# APM-PX-Adapter.net
KiCad netlist of a schematic drawn in EAGLE
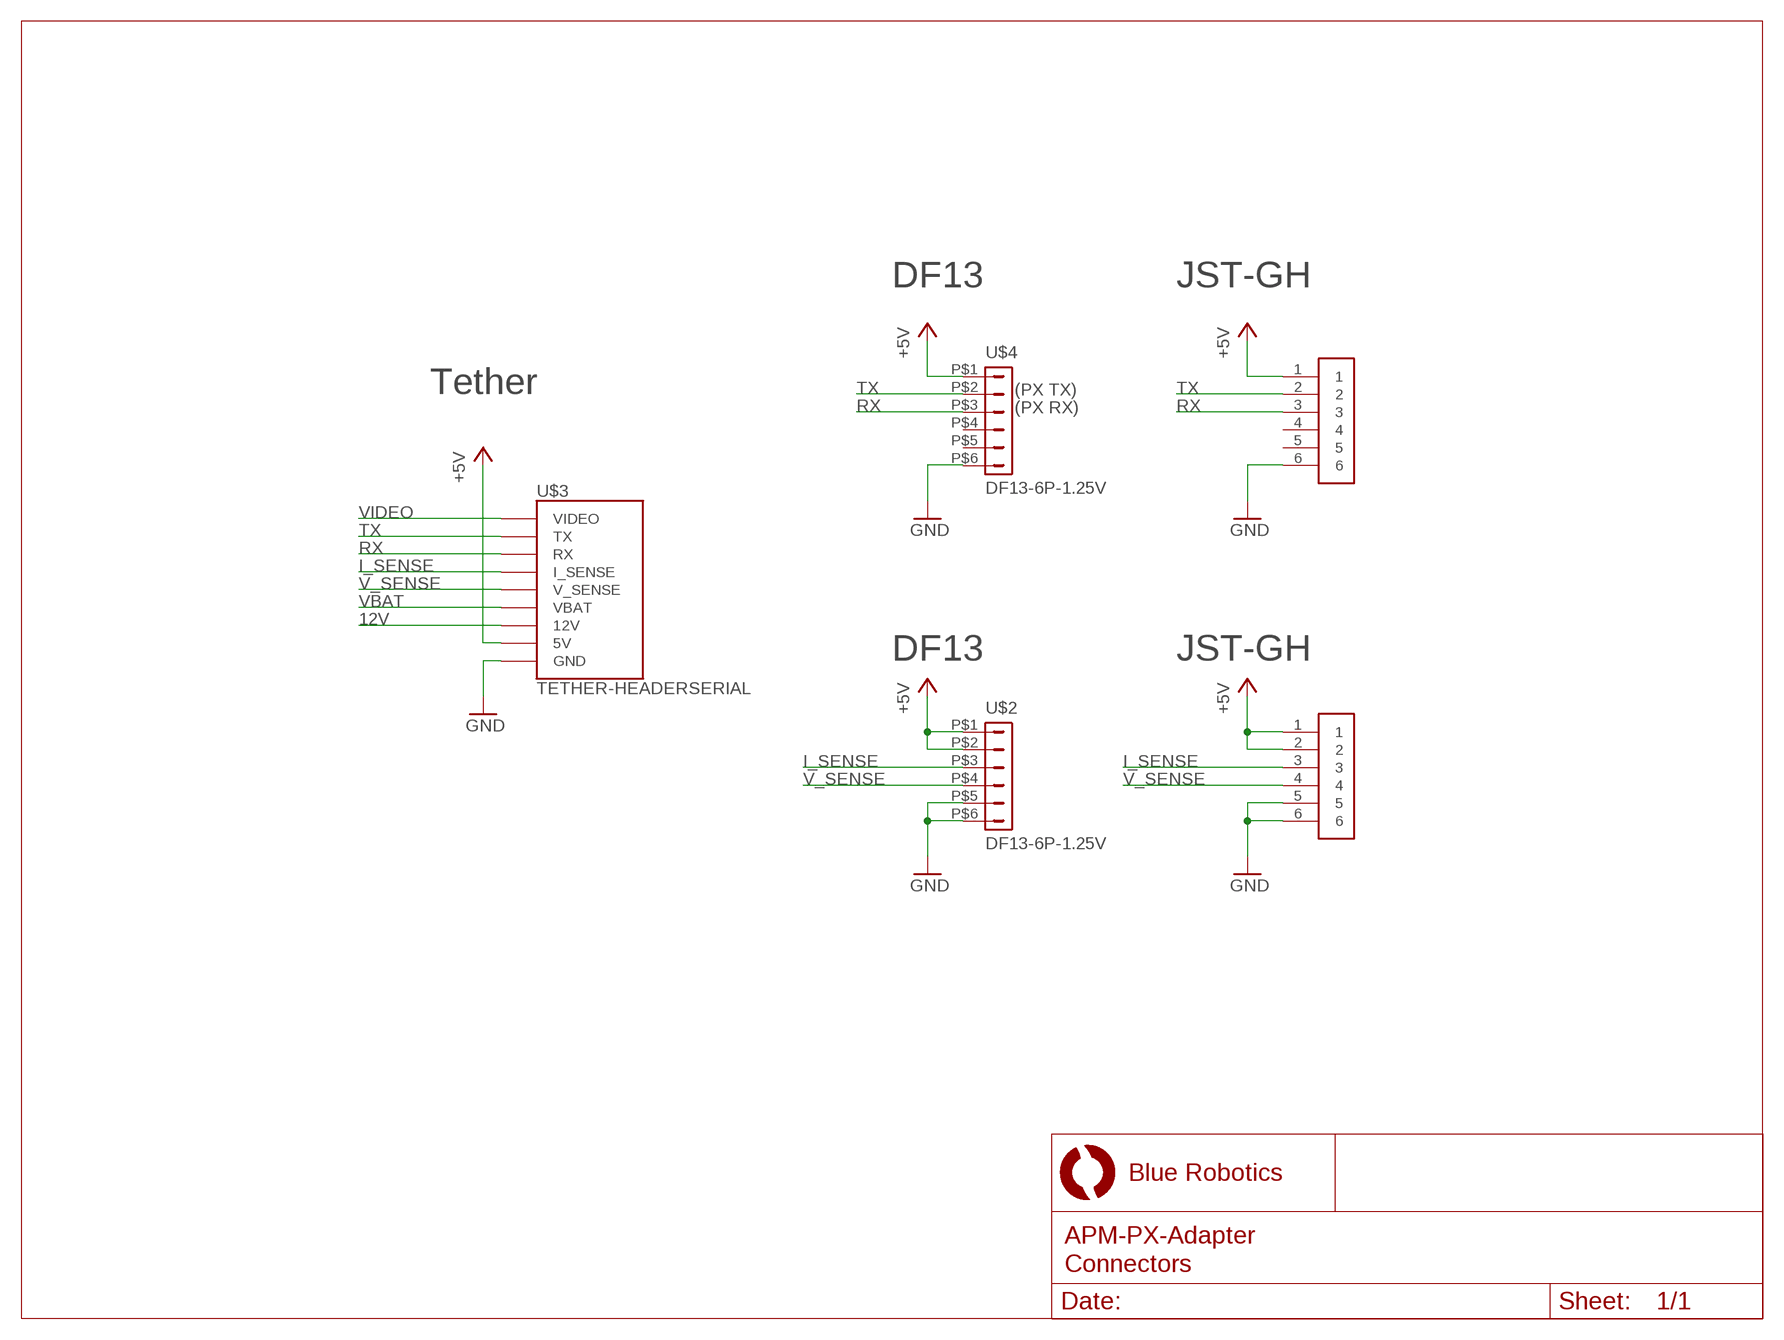
[diagram p0: schematic, sheet 1]

(export (version "E")
  (design (tool "Eeschema 10.0.6"))
  (components
    (comp (ref "U$1")
      (value "JST-GH-6TOP-ENTRY")
      (footprint "eagle-import:JST-GH-TOP-6")
      (libsource (lib "eagle-import") (part "JST-GH-6TOP-ENTRY"))
    )
    (comp (ref "U$2")
      (value "DF13-6P-1.25V")
      (footprint "eagle-import:DF13C-6P-1.25V")
      (libsource (lib "eagle-import") (part "DF13-6P-1.25V"))
    )
    (comp (ref "U$3")
      (value "TETHER-HEADERSERIAL")
      (footprint "eagle-import:TETHER-HEADER-2X7")
      (libsource (lib "eagle-import") (part "TETHER-HEADERSERIAL"))
    )
    (comp (ref "U$4")
      (value "DF13-6P-1.25V")
      (footprint "eagle-import:DF13C-6P-1.25V")
      (libsource (lib "eagle-import") (part "DF13-6P-1.25V"))
    )
    (comp (ref "U$5")
      (value "JST-GH-6TOP-ENTRY")
      (footprint "eagle-import:JST-GH-TOP-6")
      (libsource (lib "eagle-import") (part "JST-GH-6TOP-ENTRY"))
    )
  )
  (nets
    (net (code "1") (name "+5V") (class "Default")
      (node (ref "U$1") (pin "1") (pinfunction "1_1") (pintype "bidirectional"))
      (node (ref "U$2") (pin "P$1") (pinfunction "1_P$1") (pintype "passive"))
      (node (ref "U$2") (pin "P$2") (pinfunction "2_P$2") (pintype "passive"))
      (node (ref "U$3") (pin "5V") (pinfunction "5V_5V") (pintype "bidirectional"))
      (node (ref "U$4") (pin "P$1") (pinfunction "1_P$1") (pintype "passive"))
      (node (ref "U$5") (pin "1") (pinfunction "1_1") (pintype "bidirectional"))
      (node (ref "U$5") (pin "2") (pinfunction "2_2") (pintype "bidirectional"))
    )
    (net (code "2") (name "/12V") (class "Default")
      (node (ref "U$3") (pin "12V") (pinfunction "12V_12V") (pintype "bidirectional"))
    )
    (net (code "3") (name "/I_SENSE") (class "Default")
      (node (ref "U$2") (pin "P$3") (pinfunction "3_P$3") (pintype "passive"))
      (node (ref "U$3") (pin "I_SENSE") (pinfunction "I_SENSE_I_SENSE") (pintype "bidirectional"))
      (node (ref "U$5") (pin "3") (pinfunction "3_3") (pintype "bidirectional"))
    )
    (net (code "4") (name "/RX") (class "Default")
      (node (ref "U$1") (pin "3") (pinfunction "3_3") (pintype "bidirectional"))
      (node (ref "U$3") (pin "RX") (pinfunction "RX_RX") (pintype "bidirectional"))
      (node (ref "U$4") (pin "P$3") (pinfunction "3_P$3") (pintype "passive"))
    )
    (net (code "5") (name "/TX") (class "Default")
      (node (ref "U$1") (pin "2") (pinfunction "2_2") (pintype "bidirectional"))
      (node (ref "U$3") (pin "TX") (pinfunction "TX_TX") (pintype "bidirectional"))
      (node (ref "U$4") (pin "P$2") (pinfunction "2_P$2") (pintype "passive"))
    )
    (net (code "6") (name "/VBAT") (class "Default")
      (node (ref "U$3") (pin "VBAT") (pinfunction "VBAT_VBAT") (pintype "bidirectional"))
    )
    (net (code "7") (name "/VIDEO") (class "Default")
      (node (ref "U$3") (pin "VIDEO") (pinfunction "VIDEO_VIDEO") (pintype "bidirectional"))
    )
    (net (code "8") (name "/V_SENSE") (class "Default")
      (node (ref "U$2") (pin "P$4") (pinfunction "4_P$4") (pintype "passive"))
      (node (ref "U$3") (pin "V_SENSE") (pinfunction "V_SENSE_V_SENSE") (pintype "bidirectional"))
      (node (ref "U$5") (pin "4") (pinfunction "4_4") (pintype "bidirectional"))
    )
    (net (code "9") (name "GND") (class "Default")
      (node (ref "U$1") (pin "6") (pinfunction "6_6") (pintype "bidirectional"))
      (node (ref "U$2") (pin "P$5") (pinfunction "5_P$5") (pintype "passive"))
      (node (ref "U$2") (pin "P$6") (pinfunction "6_P$6") (pintype "passive"))
      (node (ref "U$3") (pin "GND0") (pinfunction "GND_GND0") (pintype "bidirectional"))
      (node (ref "U$3") (pin "GND1") (pinfunction "GND_GND1") (pintype "bidirectional"))
      (node (ref "U$3") (pin "GND2") (pinfunction "GND_GND2") (pintype "bidirectional"))
      (node (ref "U$4") (pin "P$6") (pinfunction "6_P$6") (pintype "passive"))
      (node (ref "U$5") (pin "5") (pinfunction "5_5") (pintype "bidirectional"))
      (node (ref "U$5") (pin "6") (pinfunction "6_6") (pintype "bidirectional"))
    )
    (net (code "10") (name "unconnected-(U$1-Pad4)") (class "Default")
      (node (ref "U$1") (pin "4") (pinfunction "4_4") (pintype "bidirectional"))
    )
    (net (code "11") (name "unconnected-(U$1-Pad5)") (class "Default")
      (node (ref "U$1") (pin "5") (pinfunction "5_5") (pintype "bidirectional"))
    )
    (net (code "12") (name "unconnected-(U$4-4-PadP$4)") (class "Default")
      (node (ref "U$4") (pin "P$4") (pinfunction "4_P$4") (pintype "passive"))
    )
    (net (code "13") (name "unconnected-(U$4-5-PadP$5)") (class "Default")
      (node (ref "U$4") (pin "P$5") (pinfunction "5_P$5") (pintype "passive"))
    )
  )
)
